# Papilio-Audio_Wing-v10.net
KiCad netlist of a schematic drawn in EAGLE
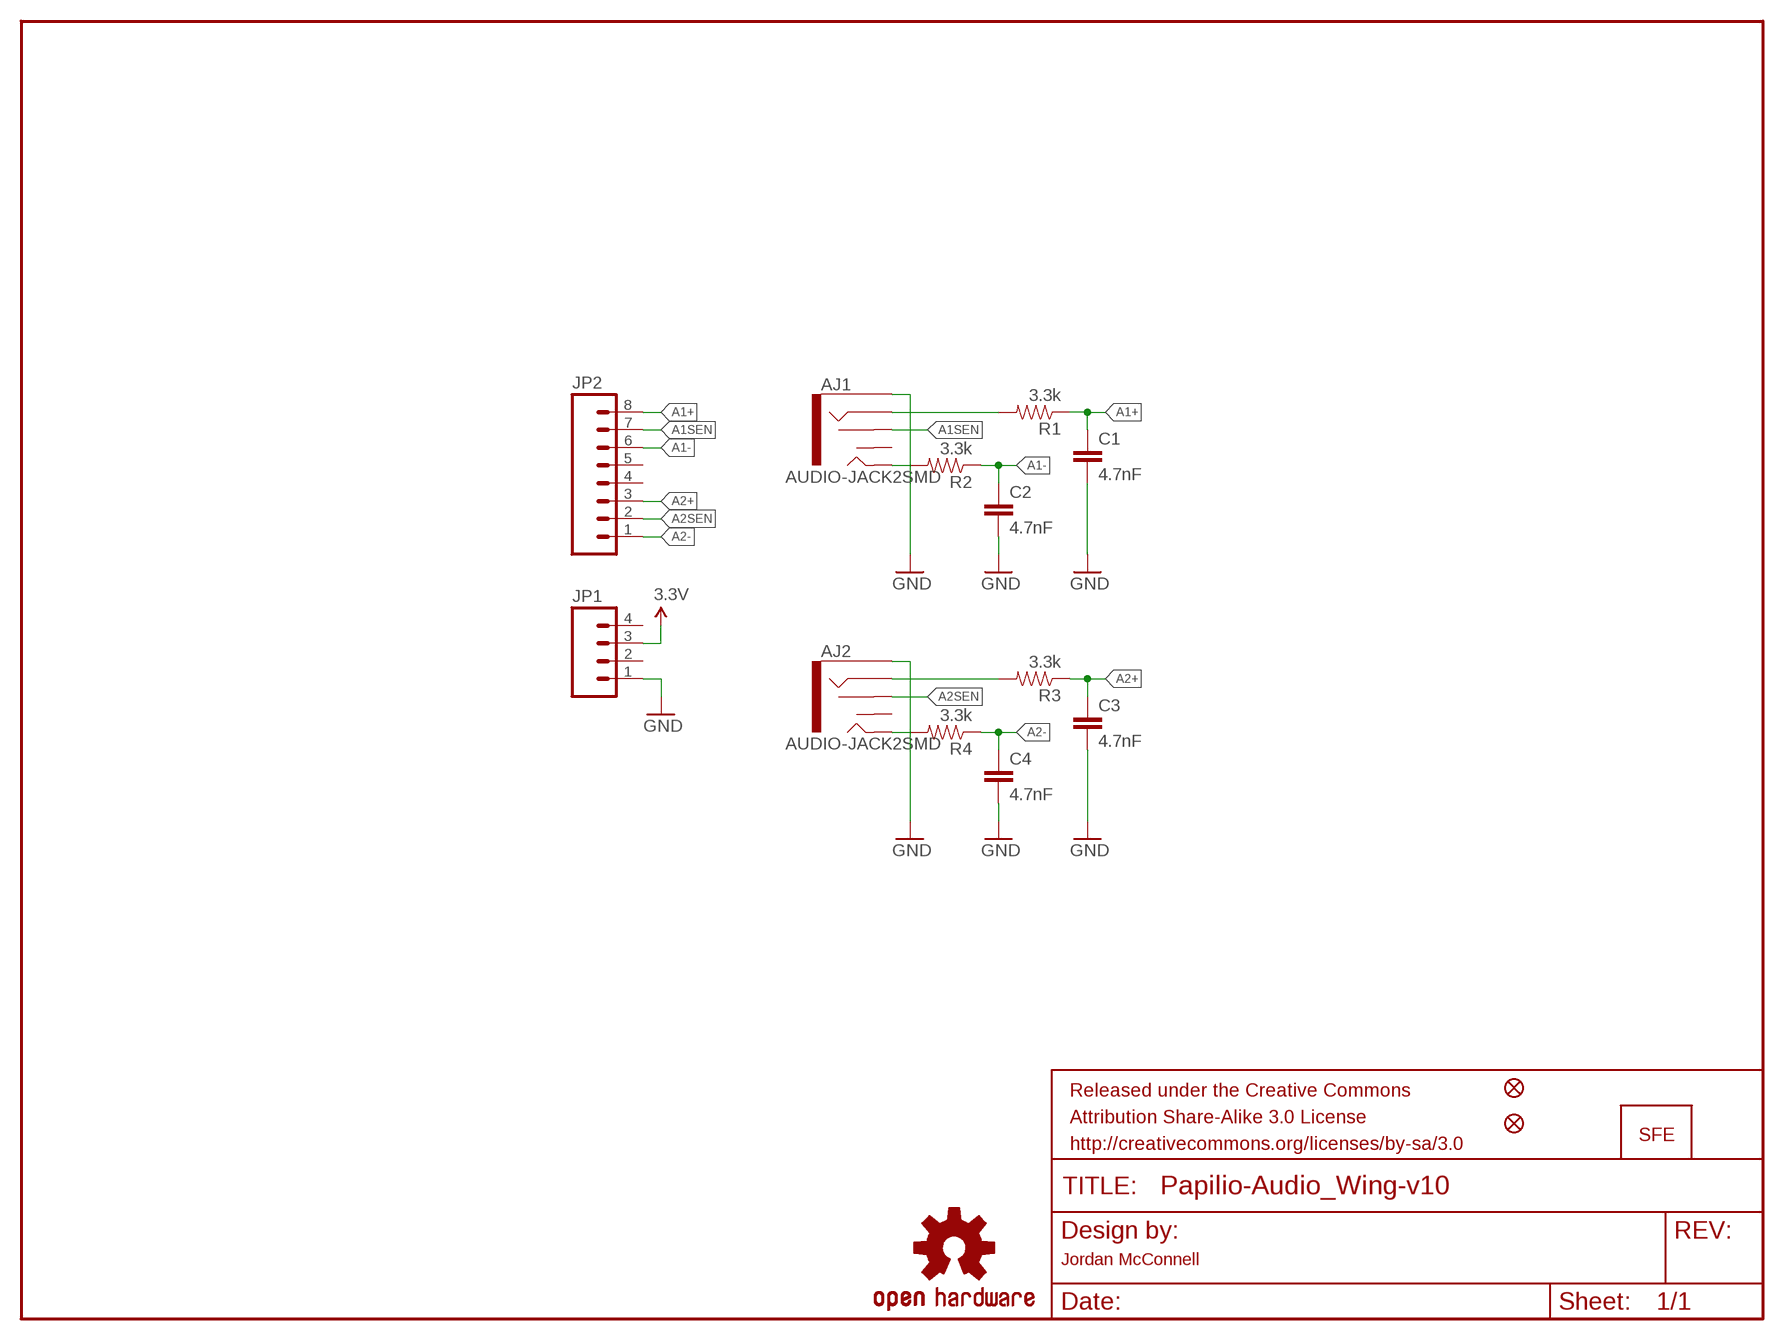
[diagram p0: schematic, sheet 1]

(export (version "E")
  (design (tool "Eeschema 10.0.6"))
  (components
    (comp (ref "AJ1")
      (value "AUDIO-JACK2SMD")
      (footprint "eagle-import:AUDIO-JACK-3.5MM-SMD")
      (libsource (lib "eagle-import") (part "AUDIO-JACK2SMD"))
    )
    (comp (ref "AJ2")
      (value "AUDIO-JACK2SMD")
      (footprint "eagle-import:AUDIO-JACK-3.5MM-SMD")
      (libsource (lib "eagle-import") (part "AUDIO-JACK2SMD"))
    )
    (comp (ref "C1")
      (value "4.7nF")
      (footprint "eagle-import:0402-CAP")
      (libsource (lib "eagle-import") (part "CAP0402-CAP"))
    )
    (comp (ref "C2")
      (value "4.7nF")
      (footprint "eagle-import:0402-CAP")
      (libsource (lib "eagle-import") (part "CAP0402-CAP"))
    )
    (comp (ref "C3")
      (value "4.7nF")
      (footprint "eagle-import:0402-CAP")
      (libsource (lib "eagle-import") (part "CAP0402-CAP"))
    )
    (comp (ref "C4")
      (value "4.7nF")
      (footprint "eagle-import:0402-CAP")
      (libsource (lib "eagle-import") (part "CAP0402-CAP"))
    )
    (comp (ref "FRAME2")
      (value "FRAME-LETTER")
      (footprint "eagle-import:CREATIVE_COMMONS")
      (libsource (lib "eagle-import") (part "FRAME-LETTER"))
    )
    (comp (ref "JP1")
      (value "M04PTH")
      (footprint "eagle-import:1X04")
      (libsource (lib "eagle-import") (part "M04PTH"))
    )
    (comp (ref "JP2")
      (value "M081X08")
      (footprint "eagle-import:1X08")
      (libsource (lib "eagle-import") (part "M081X08"))
    )
    (comp (ref "JP4")
      (value "LOGO-SFENEW")
      (footprint "eagle-import:SFE-NEW-WEBLOGO")
      (libsource (lib "eagle-import") (part "LOGO-SFENEW"))
    )
    (comp (ref "JP5")
      (value "FIDUCIALUFIDUCIAL")
      (footprint "eagle-import:MICRO-FIDUCIAL")
      (libsource (lib "eagle-import") (part "FIDUCIALUFIDUCIAL"))
    )
    (comp (ref "JP6")
      (value "FIDUCIALUFIDUCIAL")
      (footprint "eagle-import:MICRO-FIDUCIAL")
      (libsource (lib "eagle-import") (part "FIDUCIALUFIDUCIAL"))
    )
    (comp (ref "R1")
      (value "3.3k")
      (footprint "eagle-import:0402-RES")
      (libsource (lib "eagle-import") (part "RESISTOR0402-RES"))
    )
    (comp (ref "R2")
      (value "3.3k")
      (footprint "eagle-import:0402-RES")
      (libsource (lib "eagle-import") (part "RESISTOR0402-RES"))
    )
    (comp (ref "R3")
      (value "3.3k")
      (footprint "eagle-import:0402-RES")
      (libsource (lib "eagle-import") (part "RESISTOR0402-RES"))
    )
    (comp (ref "R4")
      (value "3.3k")
      (footprint "eagle-import:0402-RES")
      (libsource (lib "eagle-import") (part "RESISTOR0402-RES"))
    )
    (comp (ref "U$1")
      (value "OSHW-LOGOS")
      (footprint "eagle-import:OSHW-LOGO-S")
      (libsource (lib "eagle-import") (part "OSHW-LOGOS"))
    )
  )
  (nets
    (net (code "1") (name "3.3V") (class "Default")
      (node (ref "JP1") (pin "3") (pinfunction "3_3") (pintype "passive"))
    )
    (net (code "2") (name "A1+") (class "Default")
      (node (ref "C1") (pin "1") (pinfunction "1_1") (pintype "passive"))
      (node (ref "JP2") (pin "8") (pinfunction "8_8") (pintype "passive"))
      (node (ref "R1") (pin "1") (pinfunction "1_1") (pintype "passive"))
    )
    (net (code "3") (name "A1-") (class "Default")
      (node (ref "C2") (pin "1") (pinfunction "1_1") (pintype "passive"))
      (node (ref "JP2") (pin "6") (pinfunction "6_6") (pintype "passive"))
      (node (ref "R2") (pin "1") (pinfunction "1_1") (pintype "passive"))
    )
    (net (code "4") (name "A1SEN") (class "Default")
      (node (ref "AJ1") (pin "RSH") (pinfunction "RSH_RSH") (pintype "bidirectional"))
      (node (ref "JP2") (pin "7") (pinfunction "7_7") (pintype "passive"))
    )
    (net (code "5") (name "A2+") (class "Default")
      (node (ref "C3") (pin "1") (pinfunction "1_1") (pintype "passive"))
      (node (ref "JP2") (pin "3") (pinfunction "3_3") (pintype "passive"))
      (node (ref "R3") (pin "1") (pinfunction "1_1") (pintype "passive"))
    )
    (net (code "6") (name "A2-") (class "Default")
      (node (ref "C4") (pin "1") (pinfunction "1_1") (pintype "passive"))
      (node (ref "JP2") (pin "1") (pinfunction "1_1") (pintype "passive"))
      (node (ref "R4") (pin "1") (pinfunction "1_1") (pintype "passive"))
    )
    (net (code "7") (name "A2SEN") (class "Default")
      (node (ref "AJ2") (pin "RSH") (pinfunction "RSH_RSH") (pintype "bidirectional"))
      (node (ref "JP2") (pin "2") (pinfunction "2_2") (pintype "passive"))
    )
    (net (code "8") (name "GND") (class "Default")
      (node (ref "AJ1") (pin "SLEEVE") (pinfunction "SLEEVE_SLEEVE") (pintype "bidirectional"))
      (node (ref "AJ2") (pin "SLEEVE") (pinfunction "SLEEVE_SLEEVE") (pintype "bidirectional"))
      (node (ref "C1") (pin "2") (pinfunction "2_2") (pintype "passive"))
      (node (ref "C2") (pin "2") (pinfunction "2_2") (pintype "passive"))
      (node (ref "C3") (pin "2") (pinfunction "2_2") (pintype "passive"))
      (node (ref "C4") (pin "2") (pinfunction "2_2") (pintype "passive"))
      (node (ref "JP1") (pin "1") (pinfunction "1_1") (pintype "passive"))
    )
    (net (code "9") (name "Net-(AJ1-PadRING)") (class "Default")
      (node (ref "AJ1") (pin "RING") (pinfunction "RING_RING") (pintype "bidirectional"))
      (node (ref "R1") (pin "2") (pinfunction "2_2") (pintype "passive"))
    )
    (net (code "10") (name "Net-(AJ1-PadTIP)") (class "Default")
      (node (ref "AJ1") (pin "TIP") (pinfunction "TIP_TIP") (pintype "bidirectional"))
      (node (ref "R2") (pin "2") (pinfunction "2_2") (pintype "passive"))
    )
    (net (code "11") (name "Net-(AJ2-PadRING)") (class "Default")
      (node (ref "AJ2") (pin "RING") (pinfunction "RING_RING") (pintype "bidirectional"))
      (node (ref "R3") (pin "2") (pinfunction "2_2") (pintype "passive"))
    )
    (net (code "12") (name "Net-(AJ2-PadTIP)") (class "Default")
      (node (ref "AJ2") (pin "TIP") (pinfunction "TIP_TIP") (pintype "bidirectional"))
      (node (ref "R4") (pin "2") (pinfunction "2_2") (pintype "passive"))
    )
    (net (code "13") (name "unconnected-(AJ1-PadTSH)") (class "Default")
      (node (ref "AJ1") (pin "TSH") (pinfunction "TSH_TSH") (pintype "bidirectional"))
    )
    (net (code "14") (name "unconnected-(AJ2-PadTSH)") (class "Default")
      (node (ref "AJ2") (pin "TSH") (pinfunction "TSH_TSH") (pintype "bidirectional"))
    )
    (net (code "15") (name "unconnected-(JP1-Pad2)") (class "Default")
      (node (ref "JP1") (pin "2") (pinfunction "2_2") (pintype "passive"))
    )
    (net (code "16") (name "unconnected-(JP1-Pad4)") (class "Default")
      (node (ref "JP1") (pin "4") (pinfunction "4_4") (pintype "passive"))
    )
    (net (code "17") (name "unconnected-(JP2-Pad4)") (class "Default")
      (node (ref "JP2") (pin "4") (pinfunction "4_4") (pintype "passive"))
    )
    (net (code "18") (name "unconnected-(JP2-Pad5)") (class "Default")
      (node (ref "JP2") (pin "5") (pinfunction "5_5") (pintype "passive"))
    )
  )
)
